# Alimenta_o_v2.net
KiCad netlist of a schematic drawn in Altium Designer
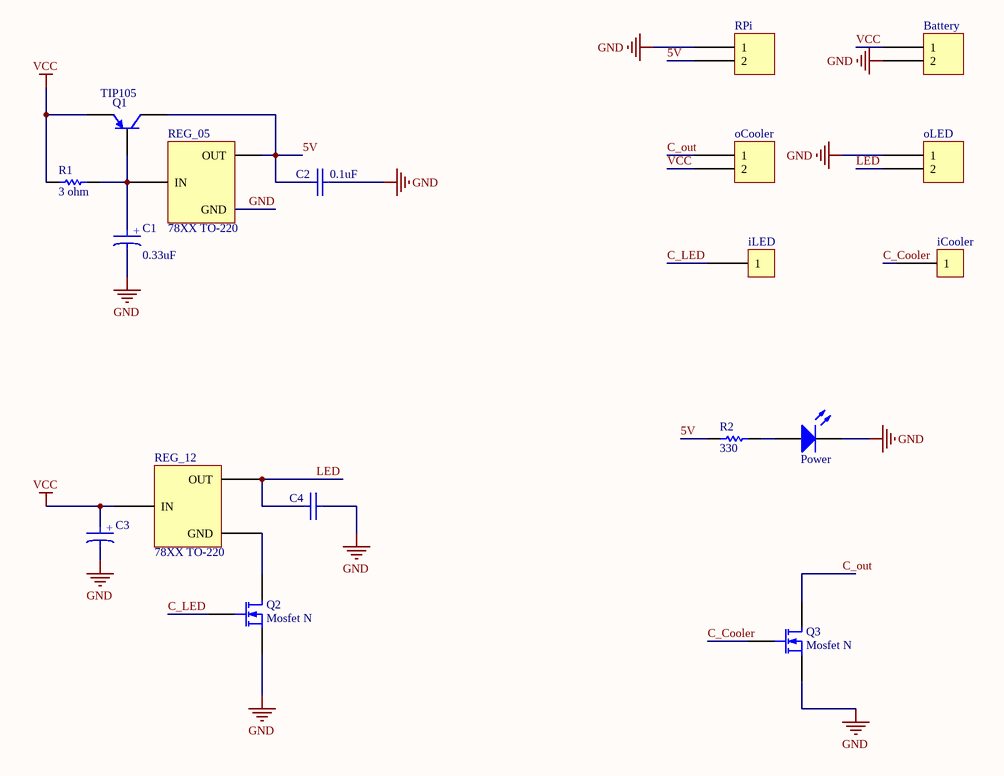
[diagram p0: Alimentação v2.SchDoc]

(export (version "E")
  (design (tool "Eeschema 10.0.6"))
  (components
    (comp (ref "Battery") (value "*") (footprint "XT90") (libsource (lib "Connectors") (part "XT90")))
    (comp (ref "C1")
      (value "0.33uF")
      (footprint "Eletrolytic Capacitor 5x5mm")
      (libsource (lib "Components") (part "Electrolytic Capacitor 0.33uF"))
    )
    (comp (ref "C2")
      (value "0.1uF")
      (footprint "SMD Capacitor")
      (libsource (lib "Components") (part "Capacitor SMD 0805"))
    )
    (comp (ref "C3")
      (value "*")
      (footprint "Eletrolytic Capacitor 5x5mm")
      (libsource (lib "Components") (part "Electrolytic Capacitor 0.33uF"))
    )
    (comp (ref "C4")
      (value "*")
      (footprint "SMD Capacitor")
      (libsource (lib "Components") (part "Capacitor SMD 0805"))
    )
    (comp (ref "iCooler")
      (value "*")
      (footprint "HEADER 1X1 8.5MM")
      (libsource (lib "Connectors") (part "Male Pin Head 1x1"))
    )
    (comp (ref "iLED")
      (value "*")
      (footprint "HEADER 1X1 8.5MM")
      (libsource (lib "Connectors") (part "Male Pin Head 1x1"))
    )
    (comp (ref "oCooler")
      (value "*")
      (footprint "KK2")
      (description "KK Connector, 2 ways")
      (libsource (lib "Connectors") (part "KK2"))
    )
    (comp (ref "oLED")
      (value "*")
      (footprint "KK2")
      (description "KK Connector, 2 ways")
      (libsource (lib "Connectors") (part "KK2"))
    )
    (comp (ref "Power")
      (value "LED 5mm THT")
      (footprint "LED THT")
      (libsource (lib "Components") (part "LED 5mm THT"))
    )
    (comp (ref "Q1")
      (value "TIP105")
      (footprint "TO-220")
      (description "PNP General Purpose Amplifier")
      (fields (field (name "PUBLISHER") "Altium Limited"))
      (libsource (lib "Miscellaneous Devices") (part "2N3906"))
    )
    (comp (ref "Q2") (value "Mosfet N") (footprint "TO-220") (libsource (lib "Components") (part "Mosfet N")))
    (comp (ref "Q3") (value "Mosfet N") (footprint "TO-220") (libsource (lib "Components") (part "Mosfet N")))
    (comp (ref "R1")
      (value "3 ohm")
      (footprint "RESISTOR THT 5mm")
      (fields (field (name "Comment") "Resistor THT"))
      (libsource (lib "Components") (part "Resistor THT"))
    )
    (comp (ref "R2")
      (value "330")
      (footprint "RESISTOR THT 5mm")
      (fields (field (name "Comment") "Resistor THT"))
      (libsource (lib "Components") (part "Resistor THT"))
    )
    (comp (ref "REG_05")
      (value "78XX TO-220")
      (footprint "TO-220")
      (libsource (lib "Components") (part "78XX TO-220"))
    )
    (comp (ref "REG_12")
      (value "78XX TO-220")
      (footprint "TO-220")
      (libsource (lib "Components") (part "78XX TO-220"))
    )
    (comp (ref "RPi")
      (value "*")
      (footprint "KK2")
      (description "KK Connector, 2 ways")
      (libsource (lib "Connectors") (part "KK2"))
    )
  )
  (nets
    (net (code "1") (name "/5V") (class "Default")
      (node (ref "C2") (pin "2") (pintype "passive"))
      (node (ref "Q1") (pin "2") (pinfunction "C_2") (pintype "passive"))
      (node (ref "R2") (pin "1") (pinfunction "1_1") (pintype "passive"))
      (node (ref "REG_05") (pin "3") (pinfunction "OUT_3") (pintype "passive"))
      (node (ref "RPi") (pin "2") (pinfunction "2_2") (pintype "passive"))
    )
    (net (code "2") (name "/C_Cooler") (class "Default")
      (node (ref "Q3") (pin "2") (pinfunction "G_2") (pintype "passive"))
      (node (ref "iCooler") (pin "1") (pinfunction "1_1") (pintype "passive"))
    )
    (net (code "3") (name "/C_LED") (class "Default")
      (node (ref "Q2") (pin "2") (pinfunction "G_2") (pintype "passive"))
      (node (ref "iLED") (pin "1") (pinfunction "1_1") (pintype "passive"))
    )
    (net (code "4") (name "/C_out") (class "Default")
      (node (ref "Q3") (pin "3") (pinfunction "D_3") (pintype "passive"))
      (node (ref "oCooler") (pin "1") (pinfunction "1_1") (pintype "passive"))
    )
    (net (code "5") (name "/LED") (class "Default")
      (node (ref "C4") (pin "2") (pintype "passive"))
      (node (ref "REG_12") (pin "3") (pinfunction "OUT_3") (pintype "passive"))
      (node (ref "oLED") (pin "2") (pinfunction "2_2") (pintype "passive"))
    )
    (net (code "6") (name "GND") (class "Default")
      (node (ref "Battery") (pin "2") (pinfunction "2_2") (pintype "passive"))
      (node (ref "C1") (pin "2") (pintype "passive"))
      (node (ref "C2") (pin "1") (pintype "passive"))
      (node (ref "C3") (pin "2") (pintype "passive"))
      (node (ref "C4") (pin "1") (pintype "passive"))
      (node (ref "Power") (pin "2") (pinfunction "K_2") (pintype "passive"))
      (node (ref "Q2") (pin "1") (pinfunction "S_1") (pintype "passive"))
      (node (ref "Q3") (pin "1") (pinfunction "S_1") (pintype "passive"))
      (node (ref "REG_05") (pin "2") (pinfunction "GND_2") (pintype "passive"))
      (node (ref "RPi") (pin "1") (pinfunction "1_1") (pintype "passive"))
      (node (ref "oLED") (pin "1") (pinfunction "1_1") (pintype "passive"))
    )
    (net (code "7") (name "Net-(Power-A)") (class "Default")
      (node (ref "Power") (pin "1") (pinfunction "A_1") (pintype "passive"))
      (node (ref "R2") (pin "2") (pinfunction "2_2") (pintype "passive"))
    )
    (net (code "8") (name "Net-(Q1-B)") (class "Default")
      (node (ref "C1") (pin "1") (pintype "passive"))
      (node (ref "Q1") (pin "3") (pinfunction "B_3") (pintype "passive"))
      (node (ref "R1") (pin "2") (pinfunction "2_2") (pintype "passive"))
      (node (ref "REG_05") (pin "1") (pinfunction "IN_1") (pintype "passive"))
    )
    (net (code "9") (name "Net-(Q2-D)") (class "Default")
      (node (ref "Q2") (pin "3") (pinfunction "D_3") (pintype "passive"))
      (node (ref "REG_12") (pin "2") (pinfunction "GND_2") (pintype "passive"))
    )
    (net (code "10") (name "VCC") (class "Default")
      (node (ref "Battery") (pin "1") (pinfunction "1_1") (pintype "passive"))
      (node (ref "C3") (pin "1") (pintype "passive"))
      (node (ref "Q1") (pin "1") (pinfunction "E_1") (pintype "passive"))
      (node (ref "R1") (pin "1") (pinfunction "1_1") (pintype "passive"))
      (node (ref "REG_12") (pin "1") (pinfunction "IN_1") (pintype "passive"))
      (node (ref "oCooler") (pin "2") (pinfunction "2_2") (pintype "passive"))
    )
  )
)
